# SoftCore_SA_P2_PG4.net
KiCad netlist of a schematic drawn in Altium Designer
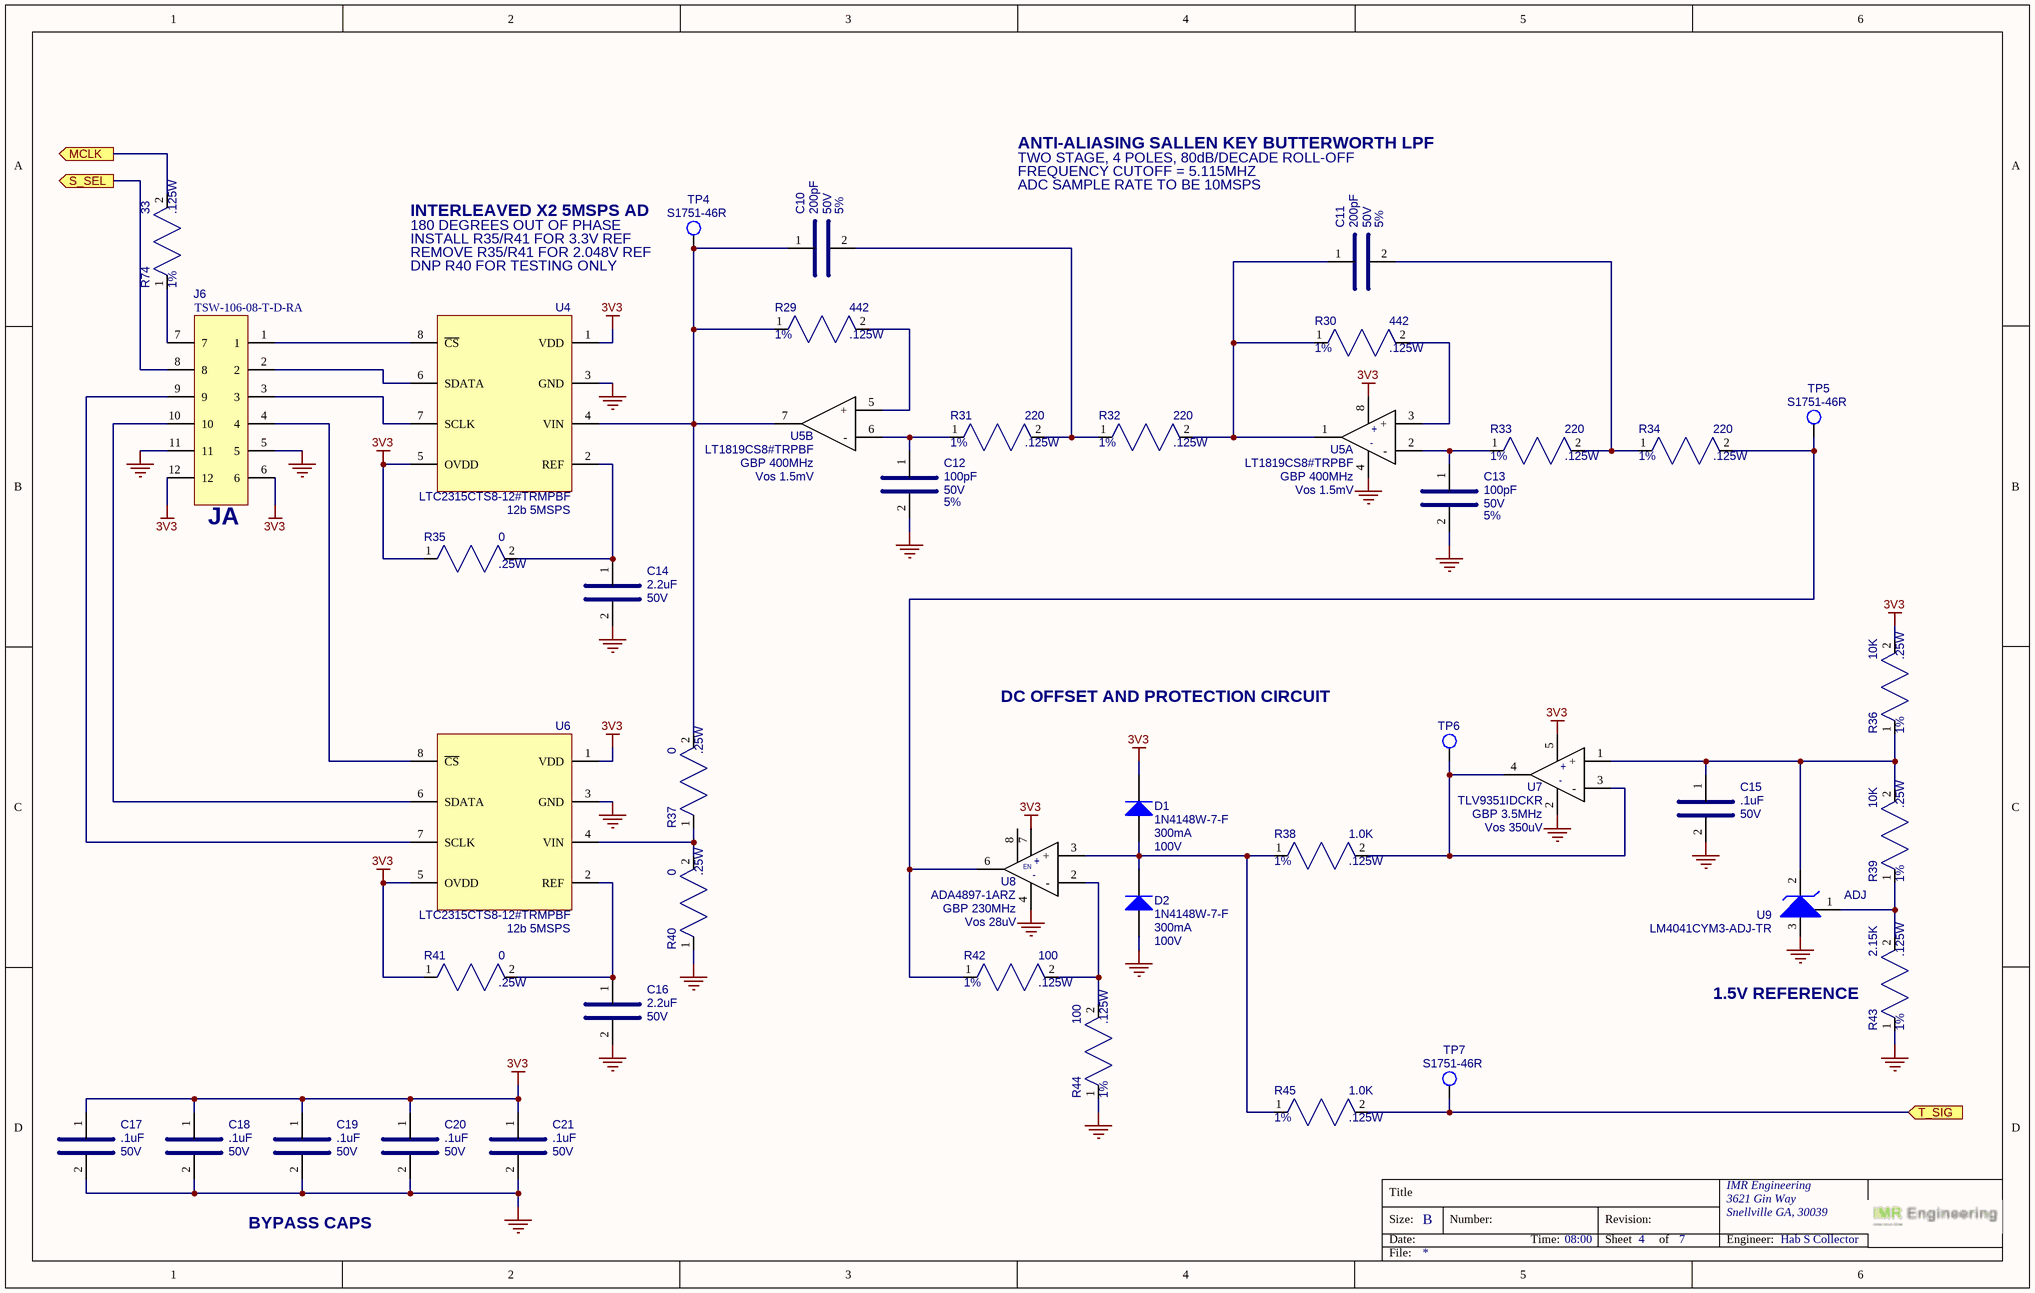
[diagram p0: SoftCore_SA_P2_PG4.SchDoc]

(export (version "E")
  (design (tool "Eeschema 10.0.6"))
  (components
    (comp (ref "C10")
      (value "200pF")
      (footprint "CAP_0805")
      (description "CAP CER 200PF 50V X7R 0805")
      (fields
        (field (name "MFG") "KEMET")
        (field (name "VOLTAGE") "50V")
        (field (name "TOLERANCE") "5%")
        (field (name "Comment") "C0805C201J5RACAUTO")
      )
      (libsource (lib "IMR_LIB_SCH_R2") (part "CAP_SMD_200PF_50V_0805"))
    )
    (comp (ref "C11")
      (value "200pF")
      (footprint "CAP_0805")
      (description "CAP CER 200PF 50V X7R 0805")
      (fields
        (field (name "MFG") "KEMET")
        (field (name "VOLTAGE") "50V")
        (field (name "TOLERANCE") "5%")
        (field (name "Comment") "C0805C201J5RACAUTO")
      )
      (libsource (lib "IMR_LIB_SCH_R2") (part "CAP_SMD_200PF_50V_0805"))
    )
    (comp (ref "C12")
      (value "100pF")
      (footprint "CAP_0805")
      (description "CAP CER 100PF 50V X7R 0805")
      (fields
        (field (name "MFG") "KEMET")
        (field (name "VOLTAGE") "50V")
        (field (name "TOLERANCE") "5%")
        (field (name "Comment") "C0805C101J5RACAUTO")
      )
      (libsource (lib "IMR_LIB_SCH_R2") (part "CAP_SMD_100PF_50V_0805"))
    )
    (comp (ref "C13")
      (value "100pF")
      (footprint "CAP_0805")
      (description "CAP CER 100PF 50V X7R 0805")
      (fields
        (field (name "MFG") "KEMET")
        (field (name "VOLTAGE") "50V")
        (field (name "TOLERANCE") "5%")
        (field (name "Comment") "C0805C101J5RACAUTO")
      )
      (libsource (lib "IMR_LIB_SCH_R2") (part "CAP_SMD_100PF_50V_0805"))
    )
    (comp (ref "C14")
      (value "2.2uF")
      (footprint "CAP_0805")
      (description "CAP CER 2.2UF 50V X5R 0805")
      (fields
        (field (name "MFG") "Murata Electronics")
        (field (name "VOLTAGE") "50V")
        (field (name "Comment") "GRM219R61E225KA12J")
      )
      (libsource (lib "IMR_LIB_SCH_R2") (part "CAP_SMD_2.2UF_50V_0805"))
    )
    (comp (ref "C15")
      (value ".1uF")
      (footprint "CAP_0805")
      (description "CAP CER 0.1UF 50V X7R 0805")
      (fields
        (field (name "MFG") "KYOCERA AVX")
        (field (name "VOLTAGE") "50V")
        (field (name "Comment") "KGM21NR71H104KT")
      )
      (libsource (lib "IMR_LIB_SCH_R2") (part "CAP_SMD_0.1UF_50V_0805"))
    )
    (comp (ref "C16")
      (value "2.2uF")
      (footprint "CAP_0805")
      (description "CAP CER 2.2UF 50V X5R 0805")
      (fields
        (field (name "MFG") "Murata Electronics")
        (field (name "VOLTAGE") "50V")
        (field (name "Comment") "GRM219R61E225KA12J")
      )
      (libsource (lib "IMR_LIB_SCH_R2") (part "CAP_SMD_2.2UF_50V_0805"))
    )
    (comp (ref "C17")
      (value ".1uF")
      (footprint "CAP_0805")
      (description "CAP CER 0.1UF 50V X7R 0805")
      (fields
        (field (name "MFG") "KYOCERA AVX")
        (field (name "VOLTAGE") "50V")
        (field (name "Comment") "KGM21NR71H104KT")
      )
      (libsource (lib "IMR_LIB_SCH_R2") (part "CAP_SMD_0.1UF_50V_0805"))
    )
    (comp (ref "C18")
      (value ".1uF")
      (footprint "CAP_0805")
      (description "CAP CER 0.1UF 50V X7R 0805")
      (fields
        (field (name "MFG") "KYOCERA AVX")
        (field (name "VOLTAGE") "50V")
        (field (name "Comment") "KGM21NR71H104KT")
      )
      (libsource (lib "IMR_LIB_SCH_R2") (part "CAP_SMD_0.1UF_50V_0805"))
    )
    (comp (ref "C19")
      (value ".1uF")
      (footprint "CAP_0805")
      (description "CAP CER 0.1UF 50V X7R 0805")
      (fields
        (field (name "MFG") "KYOCERA AVX")
        (field (name "VOLTAGE") "50V")
        (field (name "Comment") "KGM21NR71H104KT")
      )
      (libsource (lib "IMR_LIB_SCH_R2") (part "CAP_SMD_0.1UF_50V_0805"))
    )
    (comp (ref "C20")
      (value ".1uF")
      (footprint "CAP_0805")
      (description "CAP CER 0.1UF 50V X7R 0805")
      (fields
        (field (name "MFG") "KYOCERA AVX")
        (field (name "VOLTAGE") "50V")
        (field (name "Comment") "KGM21NR71H104KT")
      )
      (libsource (lib "IMR_LIB_SCH_R2") (part "CAP_SMD_0.1UF_50V_0805"))
    )
    (comp (ref "C21")
      (value ".1uF")
      (footprint "CAP_0805")
      (description "CAP CER 0.1UF 50V X7R 0805")
      (fields
        (field (name "MFG") "KYOCERA AVX")
        (field (name "VOLTAGE") "50V")
        (field (name "Comment") "KGM21NR71H104KT")
      )
      (libsource (lib "IMR_LIB_SCH_R2") (part "CAP_SMD_0.1UF_50V_0805"))
    )
    (comp (ref "D1")
      (value "100V")
      (footprint "SOD123")
      (description "RELAY REED SPDT 250MA 5V")
      (fields
        (field (name "MFG") "Diodes Inc")
        (field (name "MFG_PN") "1N4148W-7-F")
        (field (name "CURRENT") "300mA")
        (field (name "Comment") "1N4148W-7-F")
      )
      (libsource (lib "IMR_LIB_SCH_R2") (part "DIODE_1N4148W-7-F"))
    )
    (comp (ref "D2")
      (value "100V")
      (footprint "SOD123")
      (description "RELAY REED SPDT 250MA 5V")
      (fields
        (field (name "MFG") "Diodes Inc")
        (field (name "MFG_PN") "1N4148W-7-F")
        (field (name "CURRENT") "300mA")
        (field (name "Comment") "1N4148W-7-F")
      )
      (libsource (lib "IMR_LIB_SCH_R2") (part "DIODE_1N4148W-7-F"))
    )
    (comp (ref "J6")
      (value "TSW-106-08-T-D-RA")
      (footprint "SAMTEC_TSW-106-08-T-D-RA")
      (description "CONN HEADER R/A 12POS 2.54MM")
      (fields (field (name "MFG") "Samtec Inc.") (field (name "MFG_PN") "TSW-106-08-T-D-RA"))
      (libsource (lib "IMR_LIB_SCH_R2") (part "CONN_HEADER_12P_100MIL_RA"))
    )
    (comp (ref "R29")
      (value "442")
      (footprint "RES_0805")
      (description "RES SMD 442 OHM 1% 1/8W 0805")
      (fields
        (field (name "MFG") "Yageo")
        (field (name "POWER") ".125W")
        (field (name "TOLERANCE") "1%")
        (field (name "Comment") "RC0805FR-07442RL")
      )
      (libsource (lib "IMR_LIB_SCH_R2") (part "RES_SMD_442_0805_1/8W_1%"))
    )
    (comp (ref "R30")
      (value "442")
      (footprint "RES_0805")
      (description "RES SMD 442 OHM 1% 1/8W 0805")
      (fields
        (field (name "MFG") "Yageo")
        (field (name "POWER") ".125W")
        (field (name "TOLERANCE") "1%")
        (field (name "Comment") "RC0805FR-07442RL")
      )
      (libsource (lib "IMR_LIB_SCH_R2") (part "RES_SMD_442_0805_1/8W_1%"))
    )
    (comp (ref "R31")
      (value "220")
      (footprint "RES_0805")
      (description "RES SMD 220 OHM 1% 1/8W 0805")
      (fields
        (field (name "MFG") "Yageo")
        (field (name "POWER") ".125W")
        (field (name "TOLERANCE") "1%")
        (field (name "Comment") "RC0805FR-07220RL")
      )
      (libsource (lib "IMR_LIB_SCH_R2") (part "RES_SMD_220_0805_1/8W_1%"))
    )
    (comp (ref "R32")
      (value "220")
      (footprint "RES_0805")
      (description "RES SMD 220 OHM 1% 1/8W 0805")
      (fields
        (field (name "MFG") "Yageo")
        (field (name "POWER") ".125W")
        (field (name "TOLERANCE") "1%")
        (field (name "Comment") "RC0805FR-07220RL")
      )
      (libsource (lib "IMR_LIB_SCH_R2") (part "RES_SMD_220_0805_1/8W_1%"))
    )
    (comp (ref "R33")
      (value "220")
      (footprint "RES_0805")
      (description "RES SMD 220 OHM 1% 1/8W 0805")
      (fields
        (field (name "MFG") "Yageo")
        (field (name "POWER") ".125W")
        (field (name "TOLERANCE") "1%")
        (field (name "Comment") "RC0805FR-07220RL")
      )
      (libsource (lib "IMR_LIB_SCH_R2") (part "RES_SMD_220_0805_1/8W_1%"))
    )
    (comp (ref "R34")
      (value "220")
      (footprint "RES_0805")
      (description "RES SMD 220 OHM 1% 1/8W 0805")
      (fields
        (field (name "MFG") "Yageo")
        (field (name "POWER") ".125W")
        (field (name "TOLERANCE") "1%")
        (field (name "Comment") "RC0805FR-07220RL")
      )
      (libsource (lib "IMR_LIB_SCH_R2") (part "RES_SMD_220_0805_1/8W_1%"))
    )
    (comp (ref "R35")
      (value "0")
      (footprint "RES_0805")
      (description "RES SMD 0 OHM 1% 1/8W 0805")
      (fields (field (name "MFG") "Yageo") (field (name "TOLERANCE") "1%") (field (name "POWER") ".25W"))
      (libsource (lib "IMR_LIB_SCH_R2") (part "RES_SMD_0_0805_1/8W_1%"))
    )
    (comp (ref "R36")
      (value "10K")
      (footprint "RES_0805")
      (description "RES SMD 10K OHM 1% 1/4W 0805")
      (fields
        (field (name "MFG") "Yageo")
        (field (name "POWER") ".25W")
        (field (name "TOLERANCE") "1%")
        (field (name "Comment") "RC0805FR-7W10KL")
      )
      (libsource (lib "IMR_LIB_SCH_R2") (part "RES_SMD_10K_0805_1/4W_1%"))
    )
    (comp (ref "R37")
      (value "0")
      (footprint "RES_0805")
      (description "RES SMD 0 OHM 1% 1/8W 0805")
      (fields (field (name "MFG") "Yageo") (field (name "TOLERANCE") "1%") (field (name "POWER") ".25W"))
      (libsource (lib "IMR_LIB_SCH_R2") (part "RES_SMD_0_0805_1/8W_1%"))
    )
    (comp (ref "R38")
      (value "1.0K")
      (footprint "RES_0805")
      (description "RES SMD 1.0K OHM 1% 1/8W 0805")
      (fields
        (field (name "MFG") "Yageo")
        (field (name "POWER") ".125W")
        (field (name "TOLERANCE") "1%")
        (field (name "Comment") "RC0805FR-071KL")
      )
      (libsource (lib "IMR_LIB_SCH_R2") (part "RES_SMD_1.0K_0805_1/8W_1%"))
    )
    (comp (ref "R39")
      (value "10K")
      (footprint "RES_0805")
      (description "RES SMD 10K OHM 1% 1/4W 0805")
      (fields
        (field (name "MFG") "Yageo")
        (field (name "POWER") ".25W")
        (field (name "TOLERANCE") "1%")
        (field (name "Comment") "RC0805FR-7W10KL")
      )
      (libsource (lib "IMR_LIB_SCH_R2") (part "RES_SMD_10K_0805_1/4W_1%"))
    )
    (comp (ref "R40")
      (value "0")
      (footprint "RES_0805")
      (description "RES SMD 0 OHM 1% 1/8W 0805")
      (fields (field (name "MFG") "Yageo") (field (name "TOLERANCE") "1%") (field (name "POWER") ".25W"))
      (libsource (lib "IMR_LIB_SCH_R2") (part "RES_SMD_0_0805_1/8W_1%"))
    )
    (comp (ref "R41")
      (value "0")
      (footprint "RES_0805")
      (description "RES SMD 0 OHM 1% 1/8W 0805")
      (fields (field (name "MFG") "Yageo") (field (name "TOLERANCE") "1%") (field (name "POWER") ".25W"))
      (libsource (lib "IMR_LIB_SCH_R2") (part "RES_SMD_0_0805_1/8W_1%"))
    )
    (comp (ref "R42")
      (value "100")
      (footprint "RES_0805")
      (description "RES SMD 100 OHM 1% 1/8W 0805")
      (fields
        (field (name "MFG") "Yageo")
        (field (name "POWER") ".125W")
        (field (name "TOLERANCE") "1%")
        (field (name "Comment") "RC0805FR-07100RL")
      )
      (libsource (lib "IMR_LIB_SCH_R2") (part "RES_SMD_100_0805_1/8W_1%"))
    )
    (comp (ref "R43")
      (value "2.15K")
      (footprint "RES_0805")
      (description "RES SMD 2.15K OHM 1% 1/8W 0805")
      (fields
        (field (name "MFG") "Yageo")
        (field (name "POWER") ".125W")
        (field (name "TOLERANCE") "1%")
        (field (name "Comment") "RC0805FR-072K15L")
      )
      (libsource (lib "IMR_LIB_SCH_R2") (part "RES_SMD_2.15K_0805_1/8W_1%"))
    )
    (comp (ref "R44")
      (value "100")
      (footprint "RES_0805")
      (description "RES SMD 100 OHM 1% 1/8W 0805")
      (fields
        (field (name "MFG") "Yageo")
        (field (name "POWER") ".125W")
        (field (name "TOLERANCE") "1%")
        (field (name "Comment") "RC0805FR-07100RL")
      )
      (libsource (lib "IMR_LIB_SCH_R2") (part "RES_SMD_100_0805_1/8W_1%"))
    )
    (comp (ref "R45")
      (value "1.0K")
      (footprint "RES_0805")
      (description "RES SMD 1.0K OHM 1% 1/8W 0805")
      (fields
        (field (name "MFG") "Yageo")
        (field (name "POWER") ".125W")
        (field (name "TOLERANCE") "1%")
        (field (name "Comment") "RC0805FR-071KL")
      )
      (libsource (lib "IMR_LIB_SCH_R2") (part "RES_SMD_1.0K_0805_1/8W_1%"))
    )
    (comp (ref "R74")
      (value "33")
      (footprint "RES_0805")
      (description "RES SMD 33K OHM 1% 1/8W 0805")
      (fields
        (field (name "MFG") "Yageo")
        (field (name "POWER") ".125W")
        (field (name "TOLERANCE") "1%")
        (field (name "Comment") "311-33.0CRCT-ND")
      )
      (libsource (lib "IMR_LIB_SCH_R2") (part "RES_SMD_33_0805_1/8W_1%"))
    )
    (comp (ref "TP4")
      (value "S1751-46R")
      (footprint "HARWIN_S1751")
      (description "PCB TEST POINT CONNECT")
      (fields (field (name "MFG") "Harwin Inc") (field (name "MFG_PN") "S1751-46R"))
      (libsource (lib "IMR_LIB_SCH_R2") (part "CONN_TEST_POINT_S1751-46R"))
    )
    (comp (ref "TP5")
      (value "S1751-46R")
      (footprint "HARWIN_S1751")
      (description "PCB TEST POINT CONNECT")
      (fields (field (name "MFG") "Harwin Inc") (field (name "MFG_PN") "S1751-46R"))
      (libsource (lib "IMR_LIB_SCH_R2") (part "CONN_TEST_POINT_S1751-46R"))
    )
    (comp (ref "TP6")
      (value "~")
      (footprint "TEST_POINT_35MIL_TH")
      (description "TEST POINT TH FITS DSO PROBE TIP")
      (libsource (lib "IMR_LIB_SCH_R2") (part "CONN_TEST_POINT_TH_PROBE_TIP"))
    )
    (comp (ref "TP7")
      (value "S1751-46R")
      (footprint "HARWIN_S1751")
      (description "PCB TEST POINT CONNECT")
      (fields (field (name "MFG") "Harwin Inc") (field (name "MFG_PN") "S1751-46R"))
      (libsource (lib "IMR_LIB_SCH_R2") (part "CONN_TEST_POINT_S1751-46R"))
    )
    (comp (ref "U4")
      (value "12b 5MSPS")
      (footprint "SOT65P280X100-8N")
      (description "IC ADC 12BIT SAR TSOT23-8")
      (fields
        (field (name "MFG") "Analog Devices")
        (field (name "MFG_PN") "LTC2315CTS8-12#TRMPBF")
        (field (name "Comment") "LTC2315CTS8-12#TRMPBF")
      )
      (libsource (lib "IMR_LIB_SCH_R2") (part "IC_LTC2315CTS8-12#TRMPBF"))
    )
    (comp (ref "U5")
      (value "GBP 400MHz")
      (footprint "SO-8_S_LIT")
      (description "IC OPAMP GBP 400MHz CIRCUIT 8SOIC")
      (fields
        (field (name "MFG") "Analog Devices")
        (field (name "MFG_PN") "LT1819CS8#TRPBF")
        (field (name "VOS") "Vos 1.5mV")
        (field (name "Comment") "LT1819CS8#TRPBF")
      )
      (libsource (lib "IMR_LIB_SCH_R2") (part "IC_OPAMP_LT1819CS8#TRPBF"))
    )
    (comp (ref "U6")
      (value "12b 5MSPS")
      (footprint "SOT65P280X100-8N")
      (description "IC ADC 12BIT SAR TSOT23-8")
      (fields
        (field (name "MFG") "Analog Devices")
        (field (name "MFG_PN") "LTC2315CTS8-12#TRMPBF")
        (field (name "Comment") "LTC2315CTS8-12#TRMPBF")
      )
      (libsource (lib "IMR_LIB_SCH_R2") (part "IC_LTC2315CTS8-12#TRMPBF"))
    )
    (comp (ref "U7")
      (value "GBP 3.5MHz")
      (footprint "SOT-353")
      (description "IC OPAMP GP 3.5MHZ 350uV C70-5")
      (fields
        (field (name "MFG") "Texas Instruments")
        (field (name "MFG_PN") "TLV9351IDCKR")
        (field (name "VOS") "Vos 350uV")
        (field (name "Comment") "TLV9351IDCKR")
      )
      (libsource (lib "IMR_LIB_SCH_R2") (part "IC_OPAMP_TLV9351IDCKR"))
    )
    (comp (ref "U8")
      (value "GBP 230MHz")
      (footprint "R_8_ADI")
      (description "IC OPAMP GP 230MHZ 28uV 8SOIC")
      (fields
        (field (name "MFG") "Analog Devices")
        (field (name "MFG_PN") "ADA4897-1ARZ")
        (field (name "VOS") "Vos 28uV")
        (field (name "Comment") "ADA4897-1ARZ")
      )
      (libsource (lib "IMR_LIB_SCH_R2") (part "IC_OPAMP_ADA4897-1ARZ"))
    )
    (comp (ref "U9")
      (value "ADJ")
      (footprint "SOT-23")
      (description "IC VREF SHUNT ADJ 0.5% SOT23-3")
      (fields
        (field (name "MFG") "Microchip")
        (field (name "MFG_PN") "LM4041CYM3-ADJ-TR")
        (field (name "Comment") "LM4041CYM3-ADJ-TR")
      )
      (libsource (lib "IMR_LIB_SCH_R2") (part "IC_LM4041CYM3-ADJ-TR"))
    )
  )
  (nets
    (net (code "1") (name "/MCLK") (class "Default")
      (node (ref "R74") (pin "2") (pinfunction "2_2") (pintype "passive"))
    )
    (net (code "2") (name "/S_SEL") (class "Default")
      (node (ref "J6") (pin "8") (pinfunction "8_8") (pintype "passive"))
    )
    (net (code "3") (name "/T_SIG") (class "Default")
      (node (ref "R45") (pin "2") (pinfunction "2_2") (pintype "passive"))
      (node (ref "TP7") (pin "1") (pintype "passive"))
    )
    (net (code "4") (name "3V3") (class "Default")
      (node (ref "C17") (pin "1") (pinfunction "1_1") (pintype "passive"))
      (node (ref "C18") (pin "1") (pinfunction "1_1") (pintype "passive"))
      (node (ref "C19") (pin "1") (pinfunction "1_1") (pintype "passive"))
      (node (ref "C20") (pin "1") (pinfunction "1_1") (pintype "passive"))
      (node (ref "C21") (pin "1") (pinfunction "1_1") (pintype "passive"))
      (node (ref "D1") (pin "2") (pinfunction "K_2") (pintype "passive"))
      (node (ref "J6") (pin "12") (pinfunction "12_12") (pintype "passive"))
      (node (ref "J6") (pin "6") (pinfunction "6_6") (pintype "passive"))
      (node (ref "R35") (pin "1") (pinfunction "1_1") (pintype "passive"))
      (node (ref "R36") (pin "2") (pinfunction "2_2") (pintype "passive"))
      (node (ref "R41") (pin "1") (pinfunction "1_1") (pintype "passive"))
      (node (ref "U4") (pin "1") (pinfunction "VDD_1") (pintype "passive"))
      (node (ref "U4") (pin "5") (pinfunction "OVDD_5") (pintype "passive"))
      (node (ref "U5") (pin "8") (pintype "passive"))
      (node (ref "U6") (pin "1") (pinfunction "VDD_1") (pintype "passive"))
      (node (ref "U6") (pin "5") (pinfunction "OVDD_5") (pintype "passive"))
      (node (ref "U7") (pin "5") (pintype "passive"))
      (node (ref "U8") (pin "7") (pintype "passive"))
    )
    (net (code "5") (name "GND") (class "Default")
      (node (ref "C12") (pin "2") (pinfunction "2_2") (pintype "passive"))
      (node (ref "C13") (pin "2") (pinfunction "2_2") (pintype "passive"))
      (node (ref "C14") (pin "2") (pinfunction "2_2") (pintype "passive"))
      (node (ref "C15") (pin "2") (pinfunction "2_2") (pintype "passive"))
      (node (ref "C16") (pin "2") (pinfunction "2_2") (pintype "passive"))
      (node (ref "C17") (pin "2") (pinfunction "2_2") (pintype "passive"))
      (node (ref "C18") (pin "2") (pinfunction "2_2") (pintype "passive"))
      (node (ref "C19") (pin "2") (pinfunction "2_2") (pintype "passive"))
      (node (ref "C20") (pin "2") (pinfunction "2_2") (pintype "passive"))
      (node (ref "C21") (pin "2") (pinfunction "2_2") (pintype "passive"))
      (node (ref "D2") (pin "1") (pinfunction "A_1") (pintype "passive"))
      (node (ref "J6") (pin "11") (pinfunction "11_11") (pintype "passive"))
      (node (ref "J6") (pin "5") (pinfunction "5_5") (pintype "passive"))
      (node (ref "R40") (pin "1") (pinfunction "1_1") (pintype "passive"))
      (node (ref "R43") (pin "1") (pinfunction "1_1") (pintype "passive"))
      (node (ref "R44") (pin "1") (pinfunction "1_1") (pintype "passive"))
      (node (ref "U4") (pin "3") (pinfunction "GND_3") (pintype "passive"))
      (node (ref "U5") (pin "4") (pintype "passive"))
      (node (ref "U6") (pin "3") (pinfunction "GND_3") (pintype "passive"))
      (node (ref "U7") (pin "2") (pintype "passive"))
      (node (ref "U8") (pin "4") (pintype "passive"))
      (node (ref "U9") (pin "3") (pinfunction "A_3") (pintype "passive"))
    )
    (net (code "6") (name "Net-(C10-Pad2)") (class "Default")
      (node (ref "C10") (pin "2") (pinfunction "2_2") (pintype "passive"))
      (node (ref "R31") (pin "2") (pinfunction "2_2") (pintype "passive"))
      (node (ref "R32") (pin "1") (pinfunction "1_1") (pintype "passive"))
    )
    (net (code "7") (name "Net-(C11-Pad1)") (class "Default")
      (node (ref "C11") (pin "1") (pinfunction "1_1") (pintype "passive"))
      (node (ref "R30") (pin "1") (pinfunction "1_1") (pintype "passive"))
      (node (ref "R32") (pin "2") (pinfunction "2_2") (pintype "passive"))
      (node (ref "U5") (pin "1") (pintype "passive"))
    )
    (net (code "8") (name "Net-(C11-Pad2)") (class "Default")
      (node (ref "C11") (pin "2") (pinfunction "2_2") (pintype "passive"))
      (node (ref "R33") (pin "2") (pinfunction "2_2") (pintype "passive"))
      (node (ref "R34") (pin "1") (pinfunction "1_1") (pintype "passive"))
    )
    (net (code "9") (name "Net-(D1-A)") (class "Default")
      (node (ref "D1") (pin "1") (pinfunction "A_1") (pintype "passive"))
      (node (ref "D2") (pin "2") (pinfunction "K_2") (pintype "passive"))
      (node (ref "R38") (pin "1") (pinfunction "1_1") (pintype "passive"))
      (node (ref "R45") (pin "1") (pinfunction "1_1") (pintype "passive"))
      (node (ref "U8") (pin "3") (pinfunction "+_3") (pintype "passive"))
    )
    (net (code "10") (name "Net-(J6-Pad7)") (class "Default")
      (node (ref "J6") (pin "7") (pinfunction "7_7") (pintype "passive"))
      (node (ref "R74") (pin "1") (pinfunction "1_1") (pintype "passive"))
    )
    (net (code "11") (name "Net-(R34-Pad2)") (class "Default")
      (node (ref "R34") (pin "2") (pinfunction "2_2") (pintype "passive"))
      (node (ref "R42") (pin "1") (pinfunction "1_1") (pintype "passive"))
      (node (ref "TP5") (pin "1") (pintype "passive"))
      (node (ref "U8") (pin "6") (pintype "passive"))
    )
    (net (code "12") (name "Net-(U4-REF)") (class "Default")
      (node (ref "C14") (pin "1") (pinfunction "1_1") (pintype "passive"))
      (node (ref "R35") (pin "2") (pinfunction "2_2") (pintype "passive"))
      (node (ref "U4") (pin "2") (pinfunction "REF_2") (pintype "passive"))
    )
    (net (code "13") (name "Net-(U4-SCLK)") (class "Default")
      (node (ref "J6") (pin "3") (pinfunction "3_3") (pintype "passive"))
      (node (ref "U4") (pin "7") (pinfunction "SCLK_7") (pintype "passive"))
    )
    (net (code "14") (name "Net-(U4-SDATA)") (class "Default")
      (node (ref "J6") (pin "2") (pinfunction "2_2") (pintype "passive"))
      (node (ref "U4") (pin "6") (pinfunction "SDATA_6") (pintype "passive"))
    )
    (net (code "15") (name "Net-(U4-VIN)") (class "Default")
      (node (ref "C10") (pin "1") (pinfunction "1_1") (pintype "passive"))
      (node (ref "R29") (pin "1") (pinfunction "1_1") (pintype "passive"))
      (node (ref "R37") (pin "2") (pinfunction "2_2") (pintype "passive"))
      (node (ref "TP4") (pin "1") (pintype "passive"))
      (node (ref "U4") (pin "4") (pinfunction "VIN_4") (pintype "passive"))
      (node (ref "U5") (pin "7") (pintype "passive"))
    )
    (net (code "16") (name "Net-(U4-~{CS})") (class "Default")
      (node (ref "J6") (pin "1") (pinfunction "1_1") (pintype "passive"))
      (node (ref "U4") (pin "8") (pinfunction "~{CS}_8") (pintype "passive"))
    )
    (net (code "17") (name "Net-(U5A-+)") (class "Default")
      (node (ref "R30") (pin "2") (pinfunction "2_2") (pintype "passive"))
      (node (ref "U5") (pin "3") (pinfunction "+_3") (pintype "passive"))
    )
    (net (code "18") (name "Net-(U5A--)") (class "Default")
      (node (ref "C13") (pin "1") (pinfunction "1_1") (pintype "passive"))
      (node (ref "R33") (pin "1") (pinfunction "1_1") (pintype "passive"))
      (node (ref "U5") (pin "2") (pinfunction "-_2") (pintype "passive"))
    )
    (net (code "19") (name "Net-(U5B-+)") (class "Default")
      (node (ref "R29") (pin "2") (pinfunction "2_2") (pintype "passive"))
      (node (ref "U5") (pin "5") (pinfunction "+_5") (pintype "passive"))
    )
    (net (code "20") (name "Net-(U5B--)") (class "Default")
      (node (ref "C12") (pin "1") (pinfunction "1_1") (pintype "passive"))
      (node (ref "R31") (pin "1") (pinfunction "1_1") (pintype "passive"))
      (node (ref "U5") (pin "6") (pinfunction "-_6") (pintype "passive"))
    )
    (net (code "21") (name "Net-(U6-REF)") (class "Default")
      (node (ref "C16") (pin "1") (pinfunction "1_1") (pintype "passive"))
      (node (ref "R41") (pin "2") (pinfunction "2_2") (pintype "passive"))
      (node (ref "U6") (pin "2") (pinfunction "REF_2") (pintype "passive"))
    )
    (net (code "22") (name "Net-(U6-SCLK)") (class "Default")
      (node (ref "J6") (pin "9") (pinfunction "9_9") (pintype "passive"))
      (node (ref "U6") (pin "7") (pinfunction "SCLK_7") (pintype "passive"))
    )
    (net (code "23") (name "Net-(U6-SDATA)") (class "Default")
      (node (ref "J6") (pin "10") (pinfunction "10_10") (pintype "passive"))
      (node (ref "U6") (pin "6") (pinfunction "SDATA_6") (pintype "passive"))
    )
    (net (code "24") (name "Net-(U6-VIN)") (class "Default")
      (node (ref "R37") (pin "1") (pinfunction "1_1") (pintype "passive"))
      (node (ref "R40") (pin "2") (pinfunction "2_2") (pintype "passive"))
      (node (ref "U6") (pin "4") (pinfunction "VIN_4") (pintype "passive"))
    )
    (net (code "25") (name "Net-(U6-~{CS})") (class "Default")
      (node (ref "J6") (pin "4") (pinfunction "4_4") (pintype "passive"))
      (node (ref "U6") (pin "8") (pinfunction "~{CS}_8") (pintype "passive"))
    )
    (net (code "26") (name "Net-(U7-+)") (class "Default")
      (node (ref "C15") (pin "1") (pinfunction "1_1") (pintype "passive"))
      (node (ref "R36") (pin "1") (pinfunction "1_1") (pintype "passive"))
      (node (ref "R39") (pin "2") (pinfunction "2_2") (pintype "passive"))
      (node (ref "U7") (pin "1") (pinfunction "+_1") (pintype "passive"))
      (node (ref "U9") (pin "2") (pinfunction "K_2") (pintype "passive"))
    )
    (net (code "27") (name "Net-(U7--)") (class "Default")
      (node (ref "R38") (pin "2") (pinfunction "2_2") (pintype "passive"))
      (node (ref "TP6") (pin "1") (pintype "passive"))
      (node (ref "U7") (pin "3") (pinfunction "-_3") (pintype "passive"))
      (node (ref "U7") (pin "4") (pintype "passive"))
    )
    (net (code "28") (name "Net-(U8--)") (class "Default")
      (node (ref "R42") (pin "2") (pinfunction "2_2") (pintype "passive"))
      (node (ref "R44") (pin "2") (pinfunction "2_2") (pintype "passive"))
      (node (ref "U8") (pin "2") (pinfunction "-_2") (pintype "passive"))
    )
    (net (code "29") (name "Net-(U9-FB)") (class "Default")
      (node (ref "R39") (pin "1") (pinfunction "1_1") (pintype "passive"))
      (node (ref "R43") (pin "2") (pinfunction "2_2") (pintype "passive"))
      (node (ref "U9") (pin "1") (pinfunction "FB_1") (pintype "passive"))
    )
    (net (code "30") (name "unconnected-(U8-Pad8)") (class "Default")
      (node (ref "U8") (pin "8") (pintype "passive"))
    )
  )
)
